# 08usb.net
KiCad netlist of a schematic drawn in Altium Designer
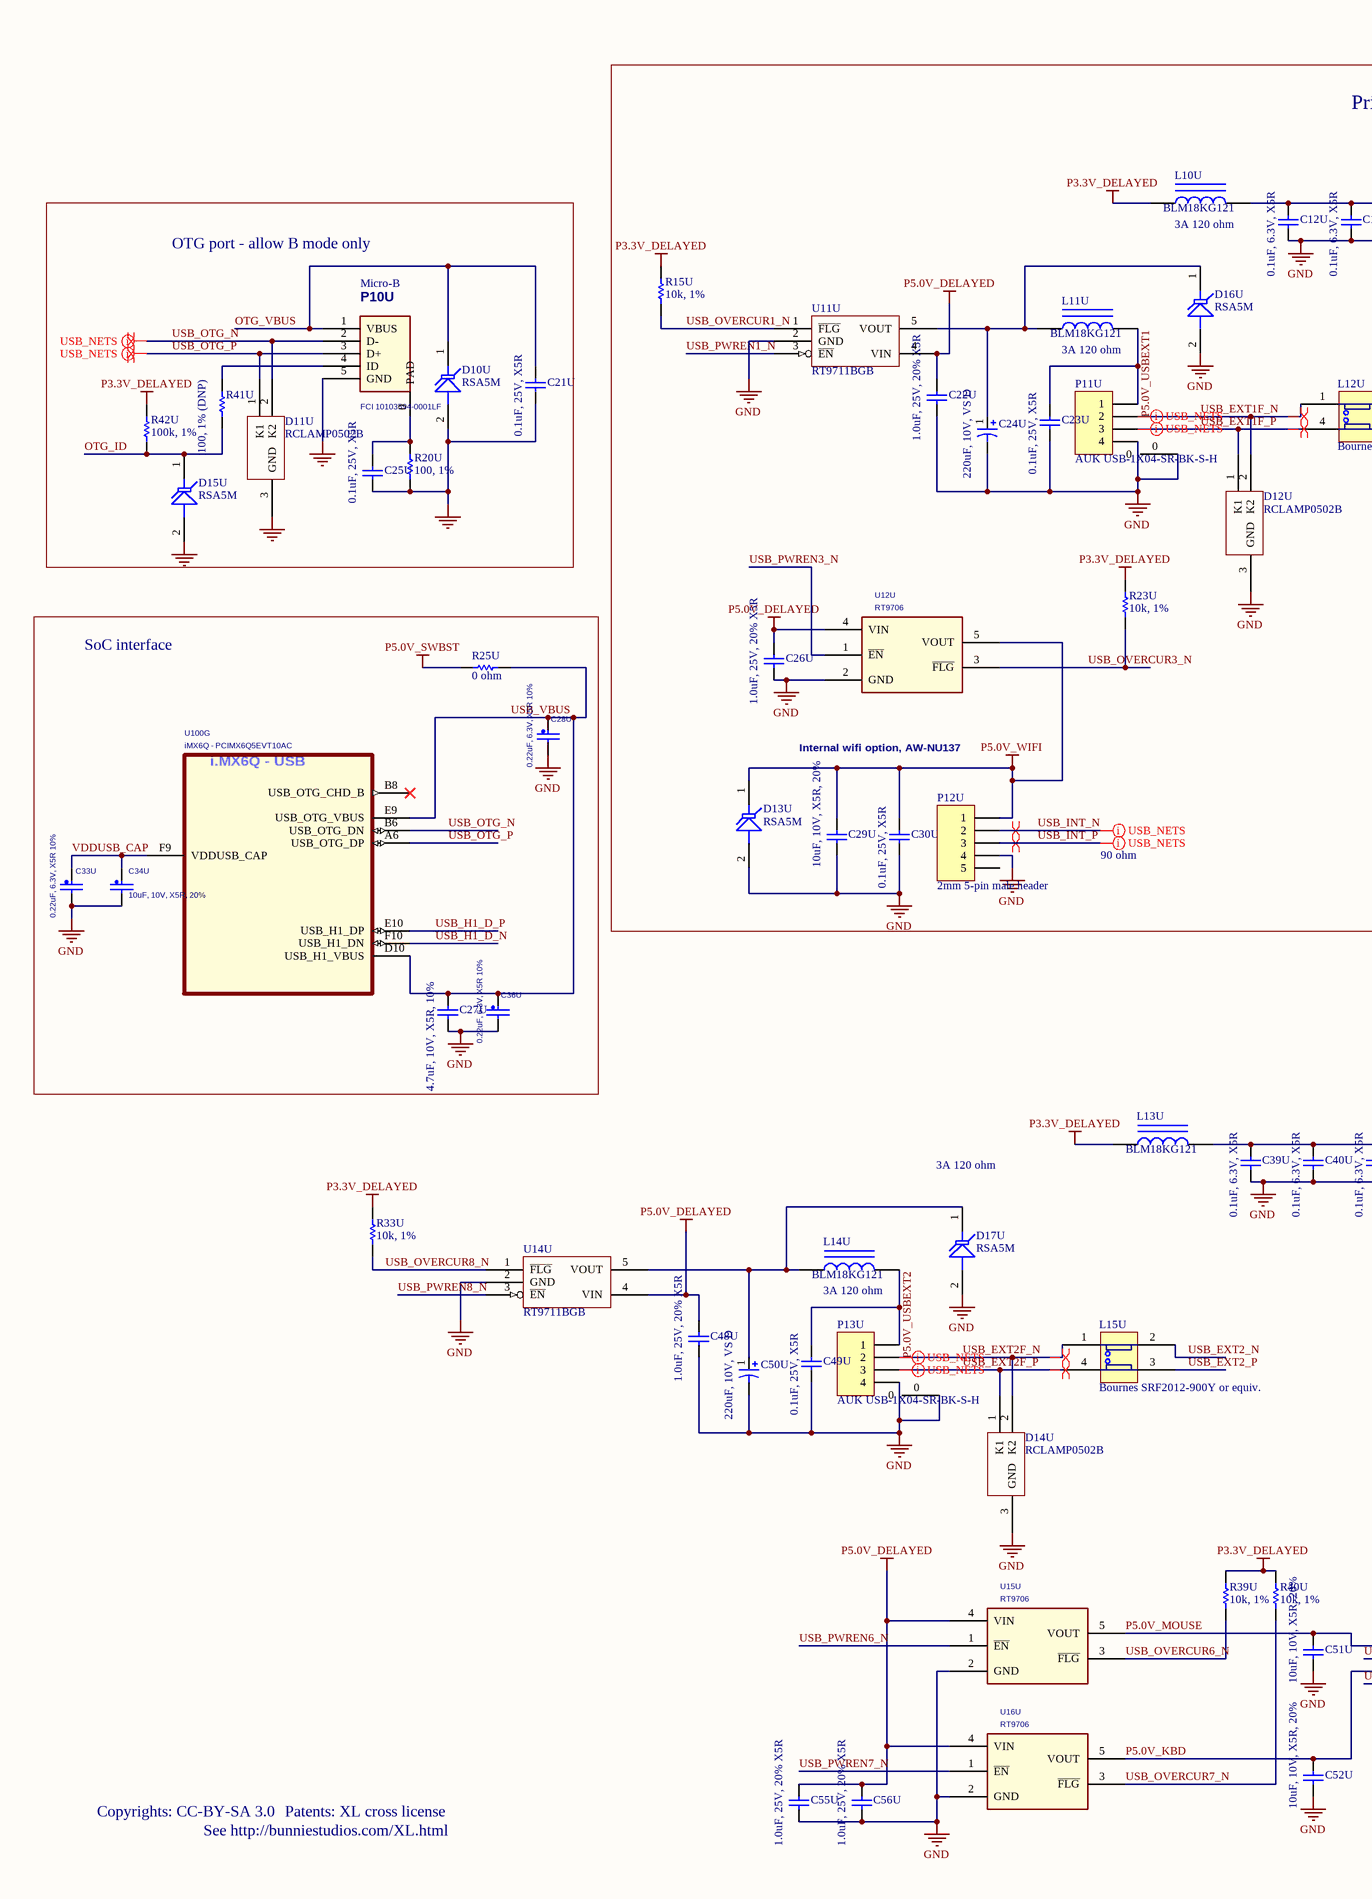
[diagram p0: 08usb.SchDoc, left]
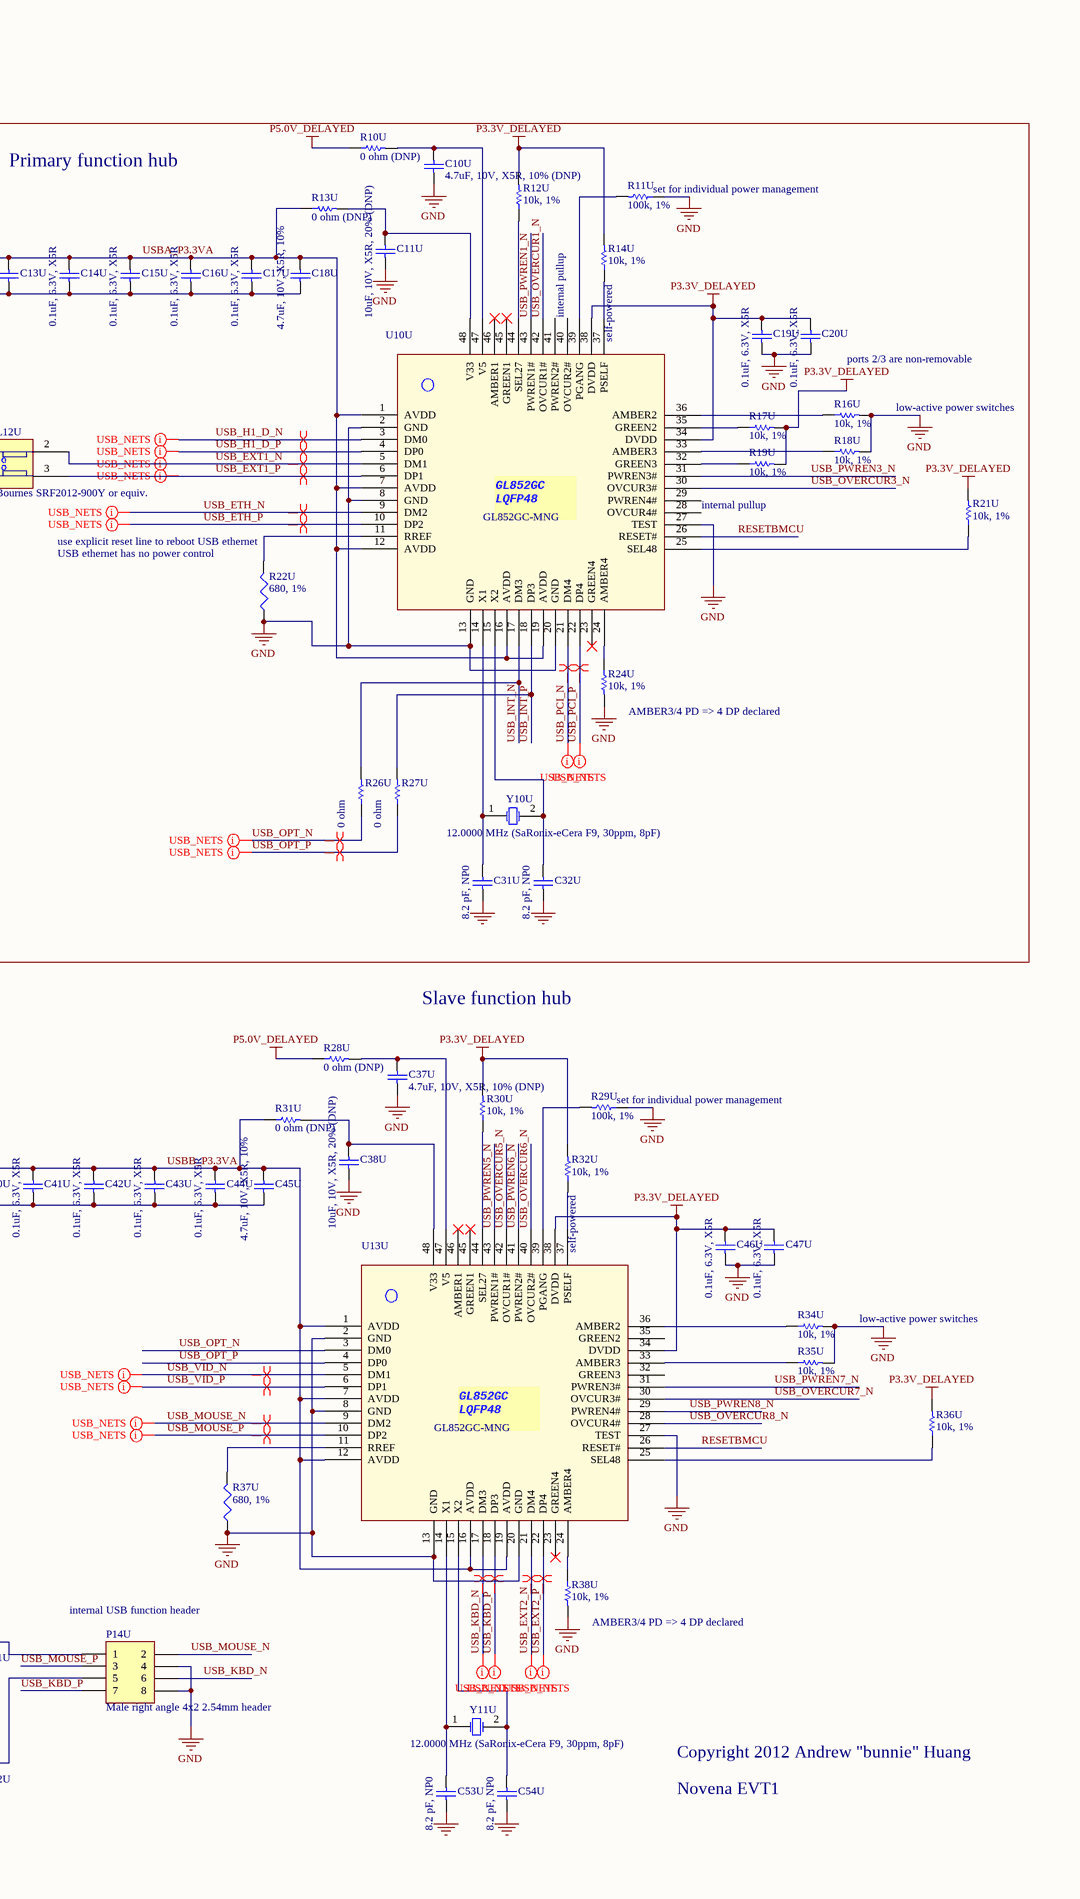
[diagram p1: 08usb.SchDoc, right]

(export (version "E")
  (design (tool "Eeschema 10.0.6"))
  (components
    (comp (ref "C10U")
      (value "4.7uF, 10V, X5R, 10% (DNP)")
      (footprint "CAPC1608N")
      (description "Capacitor (Semiconductor SIM Model)")
      (fields (field (name "PUBLISHER") "Altium Limited"))
      (libsource (lib "Miscellaneous Devices") (part "Cap Semi"))
    )
    (comp (ref "C11U")
      (value "10uF, 10V, X5R, 20% (DNP)")
      (footprint "CAPC1608N")
      (description "Capacitor (Semiconductor SIM Model)")
      (fields (field (name "PUBLISHER") "Altium Limited"))
      (libsource (lib "Miscellaneous Devices") (part "Cap Semi"))
    )
    (comp (ref "C12U")
      (value "0.1uF, 6.3V, X5R")
      (footprint "CAPC0603N_B")
      (description "Capacitor (Semiconductor SIM Model)")
      (fields (field (name "PUBLISHER") "Altium Limited"))
      (libsource (lib "Miscellaneous Devices") (part "Cap Semi"))
    )
    (comp (ref "C13U")
      (value "0.1uF, 6.3V, X5R")
      (footprint "CAPC0603N_B")
      (description "Capacitor (Semiconductor SIM Model)")
      (fields (field (name "PUBLISHER") "Altium Limited"))
      (libsource (lib "Miscellaneous Devices") (part "Cap Semi"))
    )
    (comp (ref "C14U")
      (value "0.1uF, 6.3V, X5R")
      (footprint "CAPC0603N_B")
      (description "Capacitor (Semiconductor SIM Model)")
      (fields (field (name "PUBLISHER") "Altium Limited"))
      (libsource (lib "Miscellaneous Devices") (part "Cap Semi"))
    )
    (comp (ref "C15U")
      (value "0.1uF, 6.3V, X5R")
      (footprint "CAPC0603N_B")
      (description "Capacitor (Semiconductor SIM Model)")
      (fields (field (name "PUBLISHER") "Altium Limited"))
      (libsource (lib "Miscellaneous Devices") (part "Cap Semi"))
    )
    (comp (ref "C16U")
      (value "0.1uF, 6.3V, X5R")
      (footprint "CAPC0603N_B")
      (description "Capacitor (Semiconductor SIM Model)")
      (fields (field (name "PUBLISHER") "Altium Limited"))
      (libsource (lib "Miscellaneous Devices") (part "Cap Semi"))
    )
    (comp (ref "C17U")
      (value "0.1uF, 6.3V, X5R")
      (footprint "CAPC0603N_B")
      (description "Capacitor (Semiconductor SIM Model)")
      (fields (field (name "PUBLISHER") "Altium Limited"))
      (libsource (lib "Miscellaneous Devices") (part "Cap Semi"))
    )
    (comp (ref "C18U")
      (value "4.7uF, 10V, X5R, 10%")
      (footprint "CAPC1608N")
      (description "Capacitor (Semiconductor SIM Model)")
      (fields (field (name "PUBLISHER") "Altium Limited"))
      (libsource (lib "Miscellaneous Devices") (part "Cap Semi"))
    )
    (comp (ref "C19U")
      (value "0.1uF, 6.3V, X5R")
      (footprint "CAPC0603N_B")
      (description "Capacitor (Semiconductor SIM Model)")
      (fields (field (name "PUBLISHER") "Altium Limited"))
      (libsource (lib "Miscellaneous Devices") (part "Cap Semi"))
    )
    (comp (ref "C20U")
      (value "0.1uF, 6.3V, X5R")
      (footprint "CAPC0603N_B")
      (description "Capacitor (Semiconductor SIM Model)")
      (fields (field (name "PUBLISHER") "Altium Limited"))
      (libsource (lib "Miscellaneous Devices") (part "Cap Semi"))
    )
    (comp (ref "C21U")
      (value "0.1uF, 25V, X5R")
      (footprint "CAPC1005N")
      (description "Capacitor (Semiconductor SIM Model)")
      (fields (field (name "PUBLISHER") "Altium Limited"))
      (libsource (lib "Miscellaneous Devices") (part "Cap Semi"))
    )
    (comp (ref "C22U")
      (value "1.0uF, 25V, 20% X5R")
      (footprint "CAPC1608N")
      (description "Capacitor (Semiconductor SIM Model)")
      (fields (field (name "PUBLISHER") "Altium Limited"))
      (libsource (lib "Miscellaneous Devices") (part "Cap Semi"))
    )
    (comp (ref "C23U")
      (value "0.1uF, 25V, X5R")
      (footprint "CAPC1005N")
      (description "Capacitor (Semiconductor SIM Model)")
      (fields (field (name "PUBLISHER") "Altium Limited"))
      (libsource (lib "Miscellaneous Devices") (part "Cap Semi"))
    )
    (comp (ref "C24U")
      (value "220uF, 10V, VS D")
      (footprint "6004pcb:ALCAP_D")
      (description "Polarized Capacitor (Surface Mount)")
      (fields (field (name "PUBLISHER") "Altium Limited"))
      (libsource (lib "Miscellaneous Devices") (part "Cap Pol3"))
    )
    (comp (ref "C25U")
      (value "0.1uF, 25V, X5R")
      (footprint "CAPC1005N")
      (description "Capacitor (Semiconductor SIM Model)")
      (fields (field (name "PUBLISHER") "Altium Limited"))
      (libsource (lib "Miscellaneous Devices") (part "Cap Semi"))
    )
    (comp (ref "C26U")
      (value "1.0uF, 25V, 20% X5R")
      (footprint "CAPC1608N")
      (description "Capacitor (Semiconductor SIM Model)")
      (fields (field (name "PUBLISHER") "Altium Limited"))
      (libsource (lib "Miscellaneous Devices") (part "Cap Semi"))
    )
    (comp (ref "C27U")
      (value "4.7uF, 10V, X5R, 10%")
      (footprint "CAPC1608N_HD")
      (description "Capacitor (Semiconductor SIM Model)")
      (fields (field (name "PUBLISHER") "Altium Limited"))
      (libsource (lib "Miscellaneous Devices") (part "Cap Semi"))
    )
    (comp (ref "C28U")
      (value "0.22uF, 6.3V, X5R 10%")
      (footprint "CAPC0603N_B")
      (description "CAP CER 0.01UF 6.3V 10% X7R 0201")
      (fields (field (name "TOLERANCE") "10%"))
      (libsource (lib "*") (part "CAP_NP_Dup1"))
    )
    (comp (ref "C29U")
      (value "10uF, 10V, X5R, 20%")
      (footprint "CAPC1608N")
      (description "Capacitor (Semiconductor SIM Model)")
      (fields (field (name "PUBLISHER") "Altium Limited"))
      (libsource (lib "Miscellaneous Devices") (part "Cap Semi"))
    )
    (comp (ref "C30U")
      (value "0.1uF, 25V, X5R")
      (footprint "CAPC1005N")
      (description "Capacitor (Semiconductor SIM Model)")
      (fields (field (name "PUBLISHER") "Altium Limited"))
      (libsource (lib "Miscellaneous Devices") (part "Cap Semi"))
    )
    (comp (ref "C31U")
      (value "8.2 pF, NP0")
      (footprint "CAPC1005N")
      (description "Capacitor (Semiconductor SIM Model)")
      (fields (field (name "PUBLISHER") "Altium Limited"))
      (libsource (lib "Miscellaneous Devices") (part "Cap Semi"))
    )
    (comp (ref "C32U")
      (value "8.2 pF, NP0")
      (footprint "CAPC1005N")
      (description "Capacitor (Semiconductor SIM Model)")
      (fields (field (name "PUBLISHER") "Altium Limited"))
      (libsource (lib "Miscellaneous Devices") (part "Cap Semi"))
    )
    (comp (ref "C33U")
      (value "0.22uF, 6.3V, X5R 10%")
      (footprint "CAPC0603N_B")
      (description "CAP CER 0.22UF 6.3V 20% X5R 0201")
      (fields (field (name "TOLERANCE") "20%"))
      (libsource (lib "*") (part "CAP_NP_Dup1"))
    )
    (comp (ref "C34U")
      (value "10uF, 10V, X5R, 20%")
      (footprint "CAPC1608N_HD")
      (description "CAP CER 10UF 6.3V 10% X5R 0603")
      (fields (field (name "TOLERANCE") "10%"))
      (libsource (lib "*") (part "CAP_NP_Dup1"))
    )
    (comp (ref "C36U")
      (value "0.22uF, 6.3V, X5R 10%")
      (footprint "CAPC0603N_B")
      (description "CAP CER 0.01UF 6.3V 10% X7R 0201")
      (fields (field (name "TOLERANCE") "10%"))
      (libsource (lib "*") (part "CAP_NP_Dup1"))
    )
    (comp (ref "C37U")
      (value "4.7uF, 10V, X5R, 10% (DNP)")
      (footprint "CAPC1608N")
      (description "Capacitor (Semiconductor SIM Model)")
      (fields (field (name "PUBLISHER") "Altium Limited"))
      (libsource (lib "Miscellaneous Devices") (part "Cap Semi"))
    )
    (comp (ref "C38U")
      (value "10uF, 10V, X5R, 20% (DNP)")
      (footprint "CAPC1608N")
      (description "Capacitor (Semiconductor SIM Model)")
      (fields (field (name "PUBLISHER") "Altium Limited"))
      (libsource (lib "Miscellaneous Devices") (part "Cap Semi"))
    )
    (comp (ref "C39U")
      (value "0.1uF, 6.3V, X5R")
      (footprint "CAPC0603N_B")
      (description "Capacitor (Semiconductor SIM Model)")
      (fields (field (name "PUBLISHER") "Altium Limited"))
      (libsource (lib "Miscellaneous Devices") (part "Cap Semi"))
    )
    (comp (ref "C40U")
      (value "0.1uF, 6.3V, X5R")
      (footprint "CAPC0603N_B")
      (description "Capacitor (Semiconductor SIM Model)")
      (fields (field (name "PUBLISHER") "Altium Limited"))
      (libsource (lib "Miscellaneous Devices") (part "Cap Semi"))
    )
    (comp (ref "C41U")
      (value "0.1uF, 6.3V, X5R")
      (footprint "CAPC0603N_B")
      (description "Capacitor (Semiconductor SIM Model)")
      (fields (field (name "PUBLISHER") "Altium Limited"))
      (libsource (lib "Miscellaneous Devices") (part "Cap Semi"))
    )
    (comp (ref "C42U")
      (value "0.1uF, 6.3V, X5R")
      (footprint "CAPC0603N_B")
      (description "Capacitor (Semiconductor SIM Model)")
      (fields (field (name "PUBLISHER") "Altium Limited"))
      (libsource (lib "Miscellaneous Devices") (part "Cap Semi"))
    )
    (comp (ref "C43U")
      (value "0.1uF, 6.3V, X5R")
      (footprint "CAPC0603N_B")
      (description "Capacitor (Semiconductor SIM Model)")
      (fields (field (name "PUBLISHER") "Altium Limited"))
      (libsource (lib "Miscellaneous Devices") (part "Cap Semi"))
    )
    (comp (ref "C44U")
      (value "0.1uF, 6.3V, X5R")
      (footprint "CAPC0603N_B")
      (description "Capacitor (Semiconductor SIM Model)")
      (fields (field (name "PUBLISHER") "Altium Limited"))
      (libsource (lib "Miscellaneous Devices") (part "Cap Semi"))
    )
    (comp (ref "C45U")
      (value "4.7uF, 10V, X5R, 10%")
      (footprint "CAPC1608N")
      (description "Capacitor (Semiconductor SIM Model)")
      (fields (field (name "PUBLISHER") "Altium Limited"))
      (libsource (lib "Miscellaneous Devices") (part "Cap Semi"))
    )
    (comp (ref "C46U")
      (value "0.1uF, 6.3V, X5R")
      (footprint "CAPC0603N_B")
      (description "Capacitor (Semiconductor SIM Model)")
      (fields (field (name "PUBLISHER") "Altium Limited"))
      (libsource (lib "Miscellaneous Devices") (part "Cap Semi"))
    )
    (comp (ref "C47U")
      (value "0.1uF, 6.3V, X5R")
      (footprint "CAPC0603N_B")
      (description "Capacitor (Semiconductor SIM Model)")
      (fields (field (name "PUBLISHER") "Altium Limited"))
      (libsource (lib "Miscellaneous Devices") (part "Cap Semi"))
    )
    (comp (ref "C48U")
      (value "1.0uF, 25V, 20% X5R")
      (footprint "CAPC1608N")
      (description "Capacitor (Semiconductor SIM Model)")
      (fields (field (name "PUBLISHER") "Altium Limited"))
      (libsource (lib "Miscellaneous Devices") (part "Cap Semi"))
    )
    (comp (ref "C49U")
      (value "0.1uF, 25V, X5R")
      (footprint "CAPC1005N")
      (description "Capacitor (Semiconductor SIM Model)")
      (fields (field (name "PUBLISHER") "Altium Limited"))
      (libsource (lib "Miscellaneous Devices") (part "Cap Semi"))
    )
    (comp (ref "C50U")
      (value "220uF, 10V, VS D")
      (footprint "6004pcb:ALCAP_D")
      (description "Polarized Capacitor (Surface Mount)")
      (fields (field (name "PUBLISHER") "Altium Limited"))
      (libsource (lib "Miscellaneous Devices") (part "Cap Pol3"))
    )
    (comp (ref "C51U")
      (value "10uF, 10V, X5R, 20%")
      (footprint "CAPC1608N")
      (description "Capacitor (Semiconductor SIM Model)")
      (fields (field (name "PUBLISHER") "Altium Limited"))
      (libsource (lib "Miscellaneous Devices") (part "Cap Semi"))
    )
    (comp (ref "C52U")
      (value "10uF, 10V, X5R, 20%")
      (footprint "CAPC1608N")
      (description "Capacitor (Semiconductor SIM Model)")
      (fields (field (name "PUBLISHER") "Altium Limited"))
      (libsource (lib "Miscellaneous Devices") (part "Cap Semi"))
    )
    (comp (ref "C53U")
      (value "8.2 pF, NP0")
      (footprint "CAPC1005N")
      (description "Capacitor (Semiconductor SIM Model)")
      (fields (field (name "PUBLISHER") "Altium Limited"))
      (libsource (lib "Miscellaneous Devices") (part "Cap Semi"))
    )
    (comp (ref "C54U")
      (value "8.2 pF, NP0")
      (footprint "CAPC1005N")
      (description "Capacitor (Semiconductor SIM Model)")
      (fields (field (name "PUBLISHER") "Altium Limited"))
      (libsource (lib "Miscellaneous Devices") (part "Cap Semi"))
    )
    (comp (ref "C55U")
      (value "1.0uF, 25V, 20% X5R")
      (footprint "CAPC1608N")
      (description "Capacitor (Semiconductor SIM Model)")
      (fields (field (name "PUBLISHER") "Altium Limited"))
      (libsource (lib "Miscellaneous Devices") (part "Cap Semi"))
    )
    (comp (ref "C56U")
      (value "1.0uF, 25V, 20% X5R")
      (footprint "CAPC1608N")
      (description "Capacitor (Semiconductor SIM Model)")
      (fields (field (name "PUBLISHER") "Altium Limited"))
      (libsource (lib "Miscellaneous Devices") (part "Cap Semi"))
    )
    (comp (ref "D10U")
      (value "RSA5M")
      (footprint "SOD123/X.85")
      (description "Tranzorb")
      (fields (field (name "PUBLISHER") "Altium Limited"))
      (libsource (lib "Miscellaneous Devices") (part "Tranzorb"))
    )
    (comp (ref "D11U")
      (value "RCLAMP0502B")
      (footprint "SOT-523")
      (description "2-channel ESD/CDE protection device for 5V devices")
      (libsource (lib "*") (part "RCLAMP0502B"))
    )
    (comp (ref "D12U")
      (value "RCLAMP0502B")
      (footprint "SOT-523")
      (description "2-channel ESD/CDE protection device for 5V devices")
      (libsource (lib "*") (part "RCLAMP0502B"))
    )
    (comp (ref "D13U")
      (value "RSA5M")
      (footprint "SOD123/X.85")
      (description "Tranzorb")
      (fields (field (name "PUBLISHER") "Altium Limited"))
      (libsource (lib "Miscellaneous Devices") (part "Tranzorb"))
    )
    (comp (ref "D14U")
      (value "RCLAMP0502B")
      (footprint "SOT-523")
      (description "2-channel ESD/CDE protection device for 5V devices")
      (libsource (lib "*") (part "RCLAMP0502B"))
    )
    (comp (ref "D15U")
      (value "RSA5M")
      (footprint "SOD123/X.85")
      (description "Tranzorb")
      (fields (field (name "PUBLISHER") "Altium Limited"))
      (libsource (lib "Miscellaneous Devices") (part "Tranzorb"))
    )
    (comp (ref "D16U")
      (value "RSA5M")
      (footprint "SOD123/X.85")
      (description "Tranzorb")
      (fields (field (name "PUBLISHER") "Altium Limited"))
      (libsource (lib "Miscellaneous Devices") (part "Tranzorb"))
    )
    (comp (ref "D17U")
      (value "RSA5M")
      (footprint "SOD123/X.85")
      (description "Tranzorb")
      (fields (field (name "PUBLISHER") "Altium Limited"))
      (libsource (lib "Miscellaneous Devices") (part "Tranzorb"))
    )
    (comp (ref "L10U")
      (value "BLM18KG121")
      (footprint "INDC1608AN")
      (description "Magnetic-Core Inductor")
      (fields (field (name "ALTIUM_VALUE") "3A 120 ohm") (field (name "PUBLISHER") "Altium Limited"))
      (libsource (lib "Miscellaneous Devices") (part "Inductor Iron"))
    )
    (comp (ref "L11U")
      (value "BLM18KG121")
      (footprint "INDC1608AN")
      (description "Magnetic-Core Inductor")
      (fields (field (name "ALTIUM_VALUE") "3A 120 ohm") (field (name "PUBLISHER") "Altium Limited"))
      (libsource (lib "Miscellaneous Devices") (part "Inductor Iron"))
    )
    (comp (ref "L12U")
      (value "Bournes SRF2012-900Y or equiv.")
      (footprint "USB_CM_CHOKE_0805")
      (description "USB common mode EMI choke (90 ohms)")
      (libsource (lib "commonsch") (part "USB_EMI_CHOKE"))
    )
    (comp (ref "L13U")
      (value "BLM18KG121")
      (footprint "INDC1608AN")
      (description "Magnetic-Core Inductor")
      (fields (field (name "ALTIUM_VALUE") "3A 120 ohm") (field (name "PUBLISHER") "Altium Limited"))
      (libsource (lib "Miscellaneous Devices") (part "Inductor Iron"))
    )
    (comp (ref "L14U")
      (value "BLM18KG121")
      (footprint "INDC1608AN")
      (description "Magnetic-Core Inductor")
      (fields (field (name "ALTIUM_VALUE") "3A 120 ohm") (field (name "PUBLISHER") "Altium Limited"))
      (libsource (lib "Miscellaneous Devices") (part "Inductor Iron"))
    )
    (comp (ref "L15U")
      (value "Bournes SRF2012-900Y or equiv.")
      (footprint "USB_CM_CHOKE_0805")
      (description "USB common mode EMI choke (90 ohms)")
      (libsource (lib "commonsch") (part "USB_EMI_CHOKE"))
    )
    (comp (ref "P10U")
      (value "FCI 10103594-0001LF")
      (footprint "USB_MICRO_B_SMT")
      (description "Micro USB B type connector, i.e. FCI 10103594")
      (libsource (lib "*") (part "USB_MINI-AB_1"))
    )
    (comp (ref "P11U")
      (value "AUK USB-1X04-SR-BK-S-H")
      (footprint "USB_TYPEA_TH_SINGLE")
      (description "Header, 4-Pin")
      (fields (field (name "PUBLISHER") "Altium Limited"))
      (libsource (lib "Miscellaneous Connectors") (part "Header 4"))
    )
    (comp (ref "P12U")
      (value "2mm 5-pin male header")
      (footprint "AW_NU137")
      (description "Two items: wifi card plus 5-pin, 2mm pitch male pin header, 3.5 to 4mm tall pins")
      (fields (field (name "PUBLISHER") "Altium Limited"))
      (libsource (lib "Miscellaneous Connectors") (part "Header 5"))
    )
    (comp (ref "P13U")
      (value "AUK USB-1X04-SR-BK-S-H")
      (footprint "USB_TYPEA_TH_SINGLE")
      (description "Header, 4-Pin")
      (fields (field (name "PUBLISHER") "Altium Limited"))
      (libsource (lib "Miscellaneous Connectors") (part "Header 4"))
    )
    (comp (ref "P14U")
      (value "Male right angle 4x2 2.54mm header")
      (footprint "HDR2X4H")
      (description "Header, 4-Pin, Dual row, Right Angle")
      (fields (field (name "PUBLISHER") "Altium Limited"))
      (libsource (lib "Miscellaneous Connectors") (part "Header 4X2H"))
    )
    (comp (ref "R10U")
      (value "0 ohm (DNP)")
      (footprint "RESC1005N")
      (description "Resistor")
      (fields (field (name "PUBLISHER") "Altium Limited"))
      (libsource (lib "Miscellaneous Devices") (part "Res1"))
    )
    (comp (ref "R11U")
      (value "100k, 1%")
      (footprint "RESC1005N")
      (description "Resistor")
      (fields (field (name "PUBLISHER") "Altium Limited"))
      (libsource (lib "Miscellaneous Devices") (part "Res1"))
    )
    (comp (ref "R12U")
      (value "10k, 1%")
      (footprint "RESC1005N")
      (description "Resistor")
      (fields (field (name "PUBLISHER") "Altium Limited"))
      (libsource (lib "Miscellaneous Devices") (part "Res1"))
    )
    (comp (ref "R13U")
      (value "0 ohm (DNP)")
      (footprint "RESC1005N")
      (description "Resistor")
      (fields (field (name "PUBLISHER") "Altium Limited"))
      (libsource (lib "Miscellaneous Devices") (part "Res1"))
    )
    (comp (ref "R14U")
      (value "10k, 1%")
      (footprint "RESC1005N")
      (description "Resistor")
      (fields (field (name "PUBLISHER") "Altium Limited"))
      (libsource (lib "Miscellaneous Devices") (part "Res1"))
    )
    (comp (ref "R15U")
      (value "10k, 1%")
      (footprint "RESC1005N")
      (description "Resistor")
      (fields (field (name "PUBLISHER") "Altium Limited"))
      (libsource (lib "Miscellaneous Devices") (part "Res1"))
    )
    (comp (ref "R16U")
      (value "10k, 1%")
      (footprint "RESC1005N")
      (description "Resistor")
      (fields (field (name "PUBLISHER") "Altium Limited"))
      (libsource (lib "Miscellaneous Devices") (part "Res1"))
    )
    (comp (ref "R17U")
      (value "10k, 1%")
      (footprint "RESC1005N")
      (description "Resistor")
      (fields (field (name "PUBLISHER") "Altium Limited"))
      (libsource (lib "Miscellaneous Devices") (part "Res1"))
    )
    (comp (ref "R18U")
      (value "10k, 1%")
      (footprint "RESC1005N")
      (description "Resistor")
      (fields (field (name "PUBLISHER") "Altium Limited"))
      (libsource (lib "Miscellaneous Devices") (part "Res1"))
    )
    (comp (ref "R19U")
      (value "10k, 1%")
      (footprint "RESC1005N")
      (description "Resistor")
      (fields (field (name "PUBLISHER") "Altium Limited"))
      (libsource (lib "Miscellaneous Devices") (part "Res1"))
    )
    (comp (ref "R20U")
      (value "100, 1%")
      (footprint "RESC1005N")
      (description "Resistor")
      (fields (field (name "PUBLISHER") "Altium Limited"))
      (libsource (lib "Miscellaneous Devices") (part "Res1"))
    )
    (comp (ref "R21U")
      (value "10k, 1%")
      (footprint "RESC1005N")
      (description "Resistor")
      (fields (field (name "PUBLISHER") "Altium Limited"))
      (libsource (lib "Miscellaneous Devices") (part "Res1"))
    )
    (comp (ref "R22U")
      (value "680, 1%")
      (footprint "RESC1005N")
      (description "Resistor")
      (fields (field (name "PUBLISHER") "Altium Limited"))
      (libsource (lib "Miscellaneous Devices") (part "Res3"))
    )
    (comp (ref "R23U")
      (value "10k, 1%")
      (footprint "RESC1005N")
      (description "Resistor")
      (fields (field (name "PUBLISHER") "Altium Limited"))
      (libsource (lib "Miscellaneous Devices") (part "Res1"))
    )
    (comp (ref "R24U")
      (value "10k, 1%")
      (footprint "RESC1005N")
      (description "Resistor")
      (fields (field (name "PUBLISHER") "Altium Limited"))
      (libsource (lib "Miscellaneous Devices") (part "Res1"))
    )
    (comp (ref "R25U")
      (value "0 ohm")
      (footprint "RESC1005N")
      (description "Resistor")
      (fields (field (name "PUBLISHER") "Altium Limited"))
      (libsource (lib "Miscellaneous Devices") (part "Res1"))
    )
    (comp (ref "R26U")
      (value "0 ohm")
      (footprint "RESC1005N")
      (description "Resistor")
      (fields (field (name "PUBLISHER") "Altium Limited"))
      (libsource (lib "Miscellaneous Devices") (part "Res1"))
    )
    (comp (ref "R27U")
      (value "0 ohm")
      (footprint "RESC1005N")
      (description "Resistor")
      (fields (field (name "PUBLISHER") "Altium Limited"))
      (libsource (lib "Miscellaneous Devices") (part "Res1"))
    )
    (comp (ref "R28U")
      (value "0 ohm (DNP)")
      (footprint "RESC1005N")
      (description "Resistor")
      (fields (field (name "PUBLISHER") "Altium Limited"))
      (libsource (lib "Miscellaneous Devices") (part "Res1"))
    )
    (comp (ref "R29U")
      (value "100k, 1%")
      (footprint "RESC1005N")
      (description "Resistor")
      (fields (field (name "PUBLISHER") "Altium Limited"))
      (libsource (lib "Miscellaneous Devices") (part "Res1"))
    )
    (comp (ref "R30U")
      (value "10k, 1%")
      (footprint "RESC1005N")
      (description "Resistor")
      (fields (field (name "PUBLISHER") "Altium Limited"))
      (libsource (lib "Miscellaneous Devices") (part "Res1"))
    )
    (comp (ref "R31U")
      (value "0 ohm (DNP)")
      (footprint "RESC1005N")
      (description "Resistor")
      (fields (field (name "PUBLISHER") "Altium Limited"))
      (libsource (lib "Miscellaneous Devices") (part "Res1"))
    )
    (comp (ref "R32U")
      (value "10k, 1%")
      (footprint "RESC1005N")
      (description "Resistor")
      (fields (field (name "PUBLISHER") "Altium Limited"))
      (libsource (lib "Miscellaneous Devices") (part "Res1"))
    )
    (comp (ref "R33U")
      (value "10k, 1%")
      (footprint "RESC1005N")
      (description "Resistor")
      (fields (field (name "PUBLISHER") "Altium Limited"))
      (libsource (lib "Miscellaneous Devices") (part "Res1"))
    )
    (comp (ref "R34U")
      (value "10k, 1%")
      (footprint "RESC1005N")
      (description "Resistor")
      (fields (field (name "PUBLISHER") "Altium Limited"))
      (libsource (lib "Miscellaneous Devices") (part "Res1"))
    )
    (comp (ref "R35U")
      (value "10k, 1%")
      (footprint "RESC1005N")
      (description "Resistor")
      (fields (field (name "PUBLISHER") "Altium Limited"))
      (libsource (lib "Miscellaneous Devices") (part "Res1"))
    )
    (comp (ref "R36U")
      (value "10k, 1%")
      (footprint "RESC1005N")
      (description "Resistor")
      (fields (field (name "PUBLISHER") "Altium Limited"))
      (libsource (lib "Miscellaneous Devices") (part "Res1"))
    )
    (comp (ref "R37U")
      (value "680, 1%")
      (footprint "RESC1005N")
      (description "Resistor")
      (fields (field (name "PUBLISHER") "Altium Limited"))
      (libsource (lib "Miscellaneous Devices") (part "Res3"))
    )
    (comp (ref "R38U")
      (value "10k, 1%")
      (footprint "RESC1005N")
      (description "Resistor")
      (fields (field (name "PUBLISHER") "Altium Limited"))
      (libsource (lib "Miscellaneous Devices") (part "Res1"))
    )
    (comp (ref "R39U")
      (value "10k, 1%")
      (footprint "RESC1005N")
      (description "Resistor")
      (fields (field (name "PUBLISHER") "Altium Limited"))
      (libsource (lib "Miscellaneous Devices") (part "Res1"))
    )
    (comp (ref "R40U")
      (value "10k, 1%")
      (footprint "RESC1005N")
      (description "Resistor")
      (fields (field (name "PUBLISHER") "Altium Limited"))
      (libsource (lib "Miscellaneous Devices") (part "Res1"))
    )
    (comp (ref "R41U")
      (value "100, 1% (DNP)")
      (footprint "RESC1005N")
      (description "Resistor")
      (fields (field (name "PUBLISHER") "Altium Limited"))
      (libsource (lib "Miscellaneous Devices") (part "Res1"))
    )
    (comp (ref "R42U")
      (value "100k, 1%")
      (footprint "RESC1005N")
      (description "Resistor")
      (fields (field (name "PUBLISHER") "Altium Limited"))
      (libsource (lib "Miscellaneous Devices") (part "Res1"))
    )
    (comp (ref "U10U")
      (value "GL852GC-MNG")
      (description "4-port multiple-TT hub with USB charging support")
      (libsource (lib "*") (part "GLI8024-48_4"))
    )
    (comp (ref "U11U")
      (value "RT9711BGB")
      (footprint "SOT23-5AN")
      (description "1.5A high-side power switch, active low enable")
      (libsource (lib "commonsch") (part "RT9711BGB"))
    )
    (comp (ref "U12U")
      (value "RT9706")
      (description "IC LIN SW W/FLAG 500MA 2.0-5.5V SOT23-5")
      (libsource (lib "*") (part "RT9706"))
    )
    (comp (ref "U13U")
      (value "GL852GC-MNG")
      (description "4-port multiple-TT hub with USB charging support")
      (libsource (lib "*") (part "GLI8024-48_4"))
    )
    (comp (ref "U14U")
      (value "RT9711BGB")
      (footprint "SOT23-5AN")
      (description "1.5A high-side power switch, active low enable")
      (libsource (lib "commonsch") (part "RT9711BGB"))
    )
    (comp (ref "U15U")
      (value "RT9706")
      (description "IC LIN SW W/FLAG 500MA 2.0-5.5V SOT23-5")
      (libsource (lib "*") (part "RT9706"))
    )
    (comp (ref "U16U")
      (value "RT9706")
      (description "IC LIN SW W/FLAG 500MA 2.0-5.5V SOT23-5")
      (libsource (lib "*") (part "RT9706"))
    )
    (comp (ref "U100")
      (value "iMX6Q - PCIMX6Q5EVT10AC")
      (description "PLACEHOLDER FOR FREESCALE PART NUMBER PMCIMX6Q6VV1A.")
      (libsource (lib "*") (part "PCIMX6Q6VV1A"))
    )
    (comp (ref "Y10U")
      (value "12.0000 MHz (SaRonix-eCera F9, 30ppm, 8pF)")
      (footprint "NDK_NX5032A")
      (description "Crystal Oscillator")
      (fields (field (name "PUBLISHER") "Altium Limited"))
      (libsource (lib "Miscellaneous Devices") (part "XTAL"))
    )
    (comp (ref "Y11U")
      (value "12.0000 MHz (SaRonix-eCera F9, 30ppm, 8pF)")
      (footprint "NDK_NX5032A")
      (description "Crystal Oscillator")
      (fields (field (name "PUBLISHER") "Altium Limited"))
      (libsource (lib "Miscellaneous Devices") (part "XTAL"))
    )
  )
  (nets
    (net (code "1") (name "/OTG_ID") (class "Default")
      (node (ref "D15U") (pin "1") (pinfunction "K_1") (pintype "passive"))
      (node (ref "R41U") (pin "1") (pinfunction "1_1") (pintype "passive"))
      (node (ref "R42U") (pin "1") (pinfunction "1_1") (pintype "passive"))
    )
    (net (code "2") (name "/OTG_VBUS") (class "Default")
      (node (ref "C21U") (pin "1") (pinfunction "1_1") (pintype "passive"))
      (node (ref "D10U") (pin "1") (pinfunction "K_1") (pintype "passive"))
      (node (ref "P10U") (pin "1") (pinfunction "VBUS_1") (pintype "passive"))
    )
    (net (code "3") (name "/P5.0V_KBD") (class "Default")
      (node (ref "C52U") (pin "1") (pinfunction "1_1") (pintype "passive"))
      (node (ref "P14U") (pin "5") (pinfunction "5_5") (pintype "passive"))
      (node (ref "U16U") (pin "5") (pinfunction "VOUT_5") (pintype "passive"))
    )
    (net (code "4") (name "/P5.0V_MOUSE") (class "Default")
      (node (ref "C51U") (pin "1") (pinfunction "1_1") (pintype "passive"))
      (node (ref "P14U") (pin "1") (pinfunction "1_1") (pintype "passive"))
      (node (ref "U15U") (pin "5") (pinfunction "VOUT_5") (pintype "passive"))
    )
    (net (code "5") (name "/P5.0V_USBEXT1") (class "Default")
      (node (ref "C23U") (pin "1") (pinfunction "1_1") (pintype "passive"))
      (node (ref "L11U") (pin "2") (pinfunction "2_2") (pintype "passive"))
      (node (ref "P11U") (pin "1") (pinfunction "1_1") (pintype "passive"))
    )
    (net (code "6") (name "/P5.0V_USBEXT2") (class "Default")
      (node (ref "C49U") (pin "1") (pinfunction "1_1") (pintype "passive"))
      (node (ref "L14U") (pin "2") (pinfunction "2_2") (pintype "passive"))
      (node (ref "P13U") (pin "1") (pinfunction "1_1") (pintype "passive"))
    )
    (net (code "7") (name "/RESETBMCU") (class "Default")
      (node (ref "U10U") (pin "26") (pinfunction "RESET#_26") (pintype "passive"))
      (node (ref "U13U") (pin "26") (pinfunction "RESET#_26") (pintype "passive"))
    )
    (net (code "8") (name "/USBA_P3.3VA") (class "Default")
      (node (ref "C12U") (pin "1") (pinfunction "1_1") (pintype "passive"))
      (node (ref "C13U") (pin "1") (pinfunction "1_1") (pintype "passive"))
      (node (ref "C14U") (pin "1") (pinfunction "1_1") (pintype "passive"))
      (node (ref "C15U") (pin "1") (pinfunction "1_1") (pintype "passive"))
      (node (ref "C16U") (pin "1") (pinfunction "1_1") (pintype "passive"))
      (node (ref "C17U") (pin "1") (pinfunction "1_1") (pintype "passive"))
      (node (ref "C18U") (pin "1") (pinfunction "1_1") (pintype "passive"))
      (node (ref "L10U") (pin "2") (pinfunction "2_2") (pintype "passive"))
      (node (ref "R13U") (pin "1") (pinfunction "1_1") (pintype "passive"))
      (node (ref "U10U") (pin "1") (pinfunction "AVDD_1") (pintype "passive"))
      (node (ref "U10U") (pin "12") (pinfunction "AVDD_12") (pintype "passive"))
      (node (ref "U10U") (pin "16") (pinfunction "AVDD_16") (pintype "passive"))
      (node (ref "U10U") (pin "19") (pinfunction "AVDD_19") (pintype "passive"))
      (node (ref "U10U") (pin "7") (pinfunction "AVDD_7") (pintype "passive"))
    )
    (net (code "9") (name "/USBB_P3.3VA") (class "Default")
      (node (ref "C39U") (pin "1") (pinfunction "1_1") (pintype "passive"))
      (node (ref "C40U") (pin "1") (pinfunction "1_1") (pintype "passive"))
      (node (ref "C41U") (pin "1") (pinfunction "1_1") (pintype "passive"))
      (node (ref "C42U") (pin "1") (pinfunction "1_1") (pintype "passive"))
      (node (ref "C43U") (pin "1") (pinfunction "1_1") (pintype "passive"))
      (node (ref "C44U") (pin "1") (pinfunction "1_1") (pintype "passive"))
      (node (ref "C45U") (pin "1") (pinfunction "1_1") (pintype "passive"))
      (node (ref "L13U") (pin "2") (pinfunction "2_2") (pintype "passive"))
      (node (ref "R31U") (pin "1") (pinfunction "1_1") (pintype "passive"))
      (node (ref "U13U") (pin "1") (pinfunction "AVDD_1") (pintype "passive"))
      (node (ref "U13U") (pin "12") (pinfunction "AVDD_12") (pintype "passive"))
      (node (ref "U13U") (pin "16") (pinfunction "AVDD_16") (pintype "passive"))
      (node (ref "U13U") (pin "19") (pinfunction "AVDD_19") (pintype "passive"))
      (node (ref "U13U") (pin "7") (pinfunction "AVDD_7") (pintype "passive"))
    )
    (net (code "10") (name "/USB_ETH_N") (class "Default")
      (node (ref "U10U") (pin "9") (pinfunction "DM2_9") (pintype "passive"))
    )
    (net (code "11") (name "/USB_ETH_P") (class "Default")
      (node (ref "U10U") (pin "10") (pinfunction "DP2_10") (pintype "passive"))
    )
    (net (code "12") (name "/USB_EXT1F_N") (class "Default")
      (node (ref "D12U") (pin "2") (pinfunction "K2_2") (pintype "passive"))
      (node (ref "L12U") (pin "1") (pinfunction "1_1") (pintype "passive"))
      (node (ref "P11U") (pin "2") (pinfunction "2_2") (pintype "passive"))
    )
    (net (code "13") (name "/USB_EXT1F_P") (class "Default")
      (node (ref "D12U") (pin "1") (pinfunction "K1_1") (pintype "passive"))
      (node (ref "L12U") (pin "4") (pinfunction "4_4") (pintype "passive"))
      (node (ref "P11U") (pin "3") (pinfunction "3_3") (pintype "passive"))
    )
    (net (code "14") (name "/USB_EXT1_N") (class "Default")
      (node (ref "L12U") (pin "2") (pinfunction "2_2") (pintype "passive"))
      (node (ref "U10U") (pin "5") (pinfunction "DM1_5") (pintype "passive"))
    )
    (net (code "15") (name "/USB_EXT1_P") (class "Default")
      (node (ref "L12U") (pin "3") (pinfunction "3_3") (pintype "passive"))
      (node (ref "U10U") (pin "6") (pinfunction "DP1_6") (pintype "passive"))
    )
    (net (code "16") (name "/USB_EXT2F_N") (class "Default")
      (node (ref "D14U") (pin "2") (pinfunction "K2_2") (pintype "passive"))
      (node (ref "L15U") (pin "1") (pinfunction "1_1") (pintype "passive"))
      (node (ref "P13U") (pin "2") (pinfunction "2_2") (pintype "passive"))
    )
    (net (code "17") (name "/USB_EXT2F_P") (class "Default")
      (node (ref "D14U") (pin "1") (pinfunction "K1_1") (pintype "passive"))
      (node (ref "L15U") (pin "4") (pinfunction "4_4") (pintype "passive"))
      (node (ref "P13U") (pin "3") (pinfunction "3_3") (pintype "passive"))
    )
    (net (code "18") (name "/USB_EXT2_N") (class "Default")
      (node (ref "L15U") (pin "2") (pinfunction "2_2") (pintype "passive"))
      (node (ref "U13U") (pin "21") (pinfunction "DM4_21") (pintype "passive"))
    )
    (net (code "19") (name "/USB_EXT2_P") (class "Default")
      (node (ref "L15U") (pin "3") (pinfunction "3_3") (pintype "passive"))
      (node (ref "U13U") (pin "22") (pinfunction "DP4_22") (pintype "passive"))
    )
    (net (code "20") (name "/USB_H1_D_N") (class "Default")
      (node (ref "U100") (pin "F10") (pinfunction "USB_H1_DN_F10") (pintype "bidirectional"))
      (node (ref "U10U") (pin "3") (pinfunction "DM0_3") (pintype "passive"))
    )
    (net (code "21") (name "/USB_H1_D_P") (class "Default")
      (node (ref "U100") (pin "E10") (pinfunction "USB_H1_DP_E10") (pintype "bidirectional"))
      (node (ref "U10U") (pin "4") (pinfunction "DP0_4") (pintype "passive"))
    )
    (net (code "22") (name "/USB_INT_N") (class "Default")
      (node (ref "P12U") (pin "2") (pinfunction "2_2") (pintype "passive"))
      (node (ref "R26U") (pin "2") (pinfunction "2_2") (pintype "passive"))
      (node (ref "U10U") (pin "17") (pinfunction "DM3_17") (pintype "passive"))
    )
    (net (code "23") (name "/USB_INT_P") (class "Default")
      (node (ref "P12U") (pin "3") (pinfunction "3_3") (pintype "passive"))
      (node (ref "R27U") (pin "2") (pinfunction "2_2") (pintype "passive"))
      (node (ref "U10U") (pin "18") (pinfunction "DP3_18") (pintype "passive"))
    )
    (net (code "24") (name "/USB_KBD_N") (class "Default")
      (node (ref "P14U") (pin "6") (pinfunction "6_6") (pintype "passive"))
      (node (ref "U13U") (pin "17") (pinfunction "DM3_17") (pintype "passive"))
    )
    (net (code "25") (name "/USB_KBD_P") (class "Default")
      (node (ref "P14U") (pin "7") (pinfunction "7_7") (pintype "passive"))
      (node (ref "U13U") (pin "18") (pinfunction "DP3_18") (pintype "passive"))
    )
    (net (code "26") (name "/USB_MOUSE_N") (class "Default")
      (node (ref "P14U") (pin "2") (pinfunction "2_2") (pintype "passive"))
      (node (ref "U13U") (pin "9") (pinfunction "DM2_9") (pintype "passive"))
    )
    (net (code "27") (name "/USB_MOUSE_P") (class "Default")
      (node (ref "P14U") (pin "3") (pinfunction "3_3") (pintype "passive"))
      (node (ref "U13U") (pin "10") (pinfunction "DP2_10") (pintype "passive"))
    )
    (net (code "28") (name "/USB_OPT_N") (class "Default")
      (node (ref "R26U") (pin "1") (pinfunction "1_1") (pintype "passive"))
      (node (ref "U13U") (pin "3") (pinfunction "DM0_3") (pintype "passive"))
    )
    (net (code "29") (name "/USB_OPT_P") (class "Default")
      (node (ref "R27U") (pin "1") (pinfunction "1_1") (pintype "passive"))
      (node (ref "U13U") (pin "4") (pinfunction "DP0_4") (pintype "passive"))
    )
    (net (code "30") (name "/USB_OTG_N") (class "Default")
      (node (ref "D11U") (pin "2") (pinfunction "K2_2") (pintype "passive"))
      (node (ref "P10U") (pin "2") (pinfunction "D-_2") (pintype "passive"))
      (node (ref "U100") (pin "B6") (pinfunction "USB_OTG_DN_B6") (pintype "bidirectional"))
    )
    (net (code "31") (name "/USB_OTG_P") (class "Default")
      (node (ref "D11U") (pin "1") (pinfunction "K1_1") (pintype "passive"))
      (node (ref "P10U") (pin "3") (pinfunction "D+_3") (pintype "passive"))
      (node (ref "U100") (pin "A6") (pinfunction "USB_OTG_DP_A6") (pintype "bidirectional"))
    )
    (net (code "32") (name "/USB_OVERCUR1_N") (class "Default")
      (node (ref "R15U") (pin "1") (pinfunction "1_1") (pintype "passive"))
      (node (ref "U10U") (pin "42") (pinfunction "OVCUR1#_42") (pintype "passive"))
      (node (ref "U11U") (pin "1") (pinfunction "~{FLG}_1") (pintype "open_collector"))
    )
    (net (code "33") (name "/USB_OVERCUR3_N") (class "Default")
      (node (ref "R23U") (pin "1") (pinfunction "1_1") (pintype "passive"))
      (node (ref "U10U") (pin "30") (pinfunction "OVCUR3#_30") (pintype "passive"))
      (node (ref "U12U") (pin "3") (pinfunction "~{FLG}_3") (pintype "passive"))
    )
    (net (code "34") (name "/USB_OVERCUR5_N") (class "Default")
      (node (ref "U13U") (pin "42") (pinfunction "OVCUR1#_42") (pintype "passive"))
    )
    (net (code "35") (name "/USB_OVERCUR6_N") (class "Default")
      (node (ref "R39U") (pin "2") (pinfunction "2_2") (pintype "passive"))
      (node (ref "U13U") (pin "40") (pinfunction "OVCUR2#_40") (pintype "passive"))
      (node (ref "U15U") (pin "3") (pinfunction "~{FLG}_3") (pintype "passive"))
    )
    (net (code "36") (name "/USB_OVERCUR7_N") (class "Default")
      (node (ref "R40U") (pin "2") (pinfunction "2_2") (pintype "passive"))
      (node (ref "U13U") (pin "30") (pinfunction "OVCUR3#_30") (pintype "passive"))
      (node (ref "U16U") (pin "3") (pinfunction "~{FLG}_3") (pintype "passive"))
    )
    (net (code "37") (name "/USB_OVERCUR8_N") (class "Default")
      (node (ref "R33U") (pin "1") (pinfunction "1_1") (pintype "passive"))
      (node (ref "U13U") (pin "28") (pinfunction "OVCUR4#_28") (pintype "passive"))
      (node (ref "U14U") (pin "1") (pinfunction "~{FLG}_1") (pintype "open_collector"))
    )
    (net (code "38") (name "/USB_PCI_N") (class "Default")
      (node (ref "U10U") (pin "21") (pinfunction "DM4_21") (pintype "passive"))
    )
    (net (code "39") (name "/USB_PCI_P") (class "Default")
      (node (ref "U10U") (pin "22") (pinfunction "DP4_22") (pintype "passive"))
    )
    (net (code "40") (name "/USB_PWREN1_N") (class "Default")
      (node (ref "U10U") (pin "43") (pinfunction "PWREN1#_43") (pintype "passive"))
      (node (ref "U11U") (pin "3") (pinfunction "~{EN}_3") (pintype "input"))
    )
    (net (code "41") (name "/USB_PWREN3_N") (class "Default")
      (node (ref "U10U") (pin "31") (pinfunction "PWREN3#_31") (pintype "passive"))
      (node (ref "U12U") (pin "1") (pinfunction "~{EN}_1") (pintype "passive"))
    )
    (net (code "42") (name "/USB_PWREN5_N") (class "Default")
      (node (ref "U13U") (pin "43") (pinfunction "PWREN1#_43") (pintype "passive"))
    )
    (net (code "43") (name "/USB_PWREN6_N") (class "Default")
      (node (ref "U13U") (pin "41") (pinfunction "PWREN2#_41") (pintype "passive"))
      (node (ref "U15U") (pin "1") (pinfunction "~{EN}_1") (pintype "passive"))
    )
    (net (code "44") (name "/USB_PWREN7_N") (class "Default")
      (node (ref "U13U") (pin "31") (pinfunction "PWREN3#_31") (pintype "passive"))
      (node (ref "U16U") (pin "1") (pinfunction "~{EN}_1") (pintype "passive"))
    )
    (net (code "45") (name "/USB_PWREN8_N") (class "Default")
      (node (ref "U13U") (pin "29") (pinfunction "PWREN4#_29") (pintype "passive"))
      (node (ref "U14U") (pin "3") (pinfunction "~{EN}_3") (pintype "input"))
    )
    (net (code "46") (name "/USB_VBUS") (class "Default")
      (node (ref "C27U") (pin "1") (pinfunction "1_1") (pintype "passive"))
      (node (ref "C28U") (pin "1") (pinfunction "1_1") (pintype "passive"))
      (node (ref "C36U") (pin "1") (pinfunction "1_1") (pintype "passive"))
      (node (ref "R25U") (pin "1") (pinfunction "1_1") (pintype "passive"))
      (node (ref "U100") (pin "D10") (pinfunction "USB_H1_VBUS_D10") (pintype "power_in"))
      (node (ref "U100") (pin "E9") (pinfunction "USB_OTG_VBUS_E9") (pintype "power_in"))
    )
    (net (code "47") (name "/USB_VID_N") (class "Default")
      (node (ref "U13U") (pin "5") (pinfunction "DM1_5") (pintype "passive"))
    )
    (net (code "48") (name "/USB_VID_P") (class "Default")
      (node (ref "U13U") (pin "6") (pinfunction "DP1_6") (pintype "passive"))
    )
    (net (code "49") (name "/VDDUSB_CAP") (class "Default")
      (node (ref "C33U") (pin "1") (pinfunction "1_1") (pintype "passive"))
      (node (ref "C34U") (pin "1") (pinfunction "1_1") (pintype "passive"))
      (node (ref "U100") (pin "F9") (pinfunction "VDDUSB_CAP_F9") (pintype "power_in"))
    )
    (net (code "50") (name "GND") (class "Default")
      (node (ref "C10U") (pin "2") (pinfunction "2_2") (pintype "passive"))
      (node (ref "C11U") (pin "2") (pinfunction "2_2") (pintype "passive"))
      (node (ref "C12U") (pin "2") (pinfunction "2_2") (pintype "passive"))
      (node (ref "C13U") (pin "2") (pinfunction "2_2") (pintype "passive"))
      (node (ref "C14U") (pin "2") (pinfunction "2_2") (pintype "passive"))
      (node (ref "C15U") (pin "2") (pinfunction "2_2") (pintype "passive"))
      (node (ref "C16U") (pin "2") (pinfunction "2_2") (pintype "passive"))
      (node (ref "C17U") (pin "2") (pinfunction "2_2") (pintype "passive"))
      (node (ref "C18U") (pin "2") (pinfunction "2_2") (pintype "passive"))
      (node (ref "C19U") (pin "2") (pinfunction "2_2") (pintype "passive"))
      (node (ref "C20U") (pin "2") (pinfunction "2_2") (pintype "passive"))
      (node (ref "C21U") (pin "2") (pinfunction "2_2") (pintype "passive"))
      (node (ref "C22U") (pin "2") (pinfunction "2_2") (pintype "passive"))
      (node (ref "C23U") (pin "2") (pinfunction "2_2") (pintype "passive"))
      (node (ref "C24U") (pin "2") (pinfunction "2_2") (pintype "passive"))
      (node (ref "C25U") (pin "2") (pinfunction "2_2") (pintype "passive"))
      (node (ref "C26U") (pin "2") (pinfunction "2_2") (pintype "passive"))
      (node (ref "C27U") (pin "2") (pinfunction "2_2") (pintype "passive"))
      (node (ref "C28U") (pin "2") (pinfunction "2_2") (pintype "passive"))
      (node (ref "C29U") (pin "2") (pinfunction "2_2") (pintype "passive"))
      (node (ref "C30U") (pin "2") (pinfunction "2_2") (pintype "passive"))
      (node (ref "C31U") (pin "2") (pinfunction "2_2") (pintype "passive"))
      (node (ref "C32U") (pin "2") (pinfunction "2_2") (pintype "passive"))
      (node (ref "C33U") (pin "2") (pinfunction "2_2") (pintype "passive"))
      (node (ref "C34U") (pin "2") (pinfunction "2_2") (pintype "passive"))
      (node (ref "C36U") (pin "2") (pinfunction "2_2") (pintype "passive"))
      (node (ref "C37U") (pin "2") (pinfunction "2_2") (pintype "passive"))
      (node (ref "C38U") (pin "2") (pinfunction "2_2") (pintype "passive"))
      (node (ref "C39U") (pin "2") (pinfunction "2_2") (pintype "passive"))
      (node (ref "C40U") (pin "2") (pinfunction "2_2") (pintype "passive"))
      (node (ref "C41U") (pin "2") (pinfunction "2_2") (pintype "passive"))
      (node (ref "C42U") (pin "2") (pinfunction "2_2") (pintype "passive"))
      (node (ref "C43U") (pin "2") (pinfunction "2_2") (pintype "passive"))
      (node (ref "C44U") (pin "2") (pinfunction "2_2") (pintype "passive"))
      (node (ref "C45U") (pin "2") (pinfunction "2_2") (pintype "passive"))
      (node (ref "C46U") (pin "2") (pinfunction "2_2") (pintype "passive"))
      (node (ref "C47U") (pin "2") (pinfunction "2_2") (pintype "passive"))
      (node (ref "C48U") (pin "2") (pinfunction "2_2") (pintype "passive"))
      (node (ref "C49U") (pin "2") (pinfunction "2_2") (pintype "passive"))
      (node (ref "C50U") (pin "2") (pinfunction "2_2") (pintype "passive"))
      (node (ref "C51U") (pin "2") (pinfunction "2_2") (pintype "passive"))
      (node (ref "C52U") (pin "2") (pinfunction "2_2") (pintype "passive"))
      (node (ref "C53U") (pin "2") (pinfunction "2_2") (pintype "passive"))
      (node (ref "C54U") (pin "2") (pinfunction "2_2") (pintype "passive"))
      (node (ref "C55U") (pin "2") (pinfunction "2_2") (pintype "passive"))
      (node (ref "C56U") (pin "2") (pinfunction "2_2") (pintype "passive"))
      (node (ref "D10U") (pin "2") (pinfunction "A_2") (pintype "passive"))
      (node (ref "D11U") (pin "3") (pinfunction "GND_3") (pintype "passive"))
      (node (ref "D12U") (pin "3") (pinfunction "GND_3") (pintype "passive"))
      (node (ref "D13U") (pin "2") (pinfunction "A_2") (pintype "passive"))
      (node (ref "D14U") (pin "3") (pinfunction "GND_3") (pintype "passive"))
      (node (ref "D15U") (pin "2") (pinfunction "A_2") (pintype "passive"))
      (node (ref "D16U") (pin "2") (pinfunction "A_2") (pintype "passive"))
      (node (ref "D17U") (pin "2") (pinfunction "A_2") (pintype "passive"))
      (node (ref "P10U") (pin "5") (pinfunction "GND_5") (pintype "passive"))
      (node (ref "P11U") (pin "0") (pinfunction "0_0") (pintype "passive"))
      (node (ref "P11U") (pin "4") (pinfunction "4_4") (pintype "passive"))
      (node (ref "P12U") (pin "4") (pinfunction "4_4") (pintype "passive"))
      (node (ref "P13U") (pin "0") (pinfunction "0_0") (pintype "passive"))
      (node (ref "P13U") (pin "4") (pinfunction "4_4") (pintype "passive"))
      (node (ref "P14U") (pin "4") (pinfunction "4_4") (pintype "passive"))
      (node (ref "P14U") (pin "8") (pinfunction "8_8") (pintype "passive"))
      (node (ref "R11U") (pin "1") (pinfunction "1_1") (pintype "passive"))
      (node (ref "R16U") (pin "2") (pinfunction "2_2") (pintype "passive"))
      (node (ref "R18U") (pin "2") (pinfunction "2_2") (pintype "passive"))
      (node (ref "R20U") (pin "2") (pinfunction "2_2") (pintype "passive"))
      (node (ref "R22U") (pin "1") (pinfunction "1_1") (pintype "passive"))
      (node (ref "R24U") (pin "2") (pinfunction "2_2") (pintype "passive"))
      (node (ref "R29U") (pin "1") (pinfunction "1_1") (pintype "passive"))
      (node (ref "R34U") (pin "2") (pinfunction "2_2") (pintype "passive"))
      (node (ref "R35U") (pin "2") (pinfunction "2_2") (pintype "passive"))
      (node (ref "R37U") (pin "1") (pinfunction "1_1") (pintype "passive"))
      (node (ref "R38U") (pin "2") (pinfunction "2_2") (pintype "passive"))
      (node (ref "U10U") (pin "13") (pinfunction "GND_13") (pintype "passive"))
      (node (ref "U10U") (pin "2") (pinfunction "GND_2") (pintype "passive"))
      (node (ref "U10U") (pin "20") (pinfunction "GND_20") (pintype "passive"))
      (node (ref "U10U") (pin "27") (pinfunction "TEST_27") (pintype "passive"))
      (node (ref "U10U") (pin "8") (pinfunction "GND_8") (pintype "passive"))
      (node (ref "U11U") (pin "2") (pinfunction "GND_2") (pintype "power_in"))
      (node (ref "U12U") (pin "2") (pinfunction "GND_2") (pintype "power_in"))
      (node (ref "U13U") (pin "13") (pinfunction "GND_13") (pintype "passive"))
      (node (ref "U13U") (pin "2") (pinfunction "GND_2") (pintype "passive"))
      (node (ref "U13U") (pin "20") (pinfunction "GND_20") (pintype "passive"))
      (node (ref "U13U") (pin "27") (pinfunction "TEST_27") (pintype "passive"))
      (node (ref "U13U") (pin "8") (pinfunction "GND_8") (pintype "passive"))
      (node (ref "U14U") (pin "2") (pinfunction "GND_2") (pintype "power_in"))
      (node (ref "U15U") (pin "2") (pinfunction "GND_2") (pintype "power_in"))
      (node (ref "U16U") (pin "2") (pinfunction "GND_2") (pintype "power_in"))
    )
    (net (code "51") (name "Net-(D16U-K)") (class "Default")
      (node (ref "C24U") (pin "1") (pinfunction "1_1") (pintype "passive"))
      (node (ref "D16U") (pin "1") (pinfunction "K_1") (pintype "passive"))
      (node (ref "L11U") (pin "1") (pinfunction "1_1") (pintype "passive"))
      (node (ref "U11U") (pin "5") (pinfunction "VOUT_5") (pintype "power_in"))
    )
    (net (code "52") (name "Net-(D17U-K)") (class "Default")
      (node (ref "C50U") (pin "1") (pinfunction "1_1") (pintype "passive"))
      (node (ref "D17U") (pin "1") (pinfunction "K_1") (pintype "passive"))
      (node (ref "L14U") (pin "1") (pinfunction "1_1") (pintype "passive"))
      (node (ref "U14U") (pin "5") (pinfunction "VOUT_5") (pintype "power_in"))
    )
    (net (code "53") (name "Net-(P10U-ID)") (class "Default")
      (node (ref "P10U") (pin "4") (pinfunction "ID_4") (pintype "passive"))
      (node (ref "R41U") (pin "2") (pinfunction "2_2") (pintype "passive"))
    )
    (net (code "54") (name "Net-(P10U-PAD)") (class "Default")
      (node (ref "C25U") (pin "1") (pinfunction "1_1") (pintype "passive"))
      (node (ref "P10U") (pin "0") (pinfunction "PAD_0") (pintype "passive"))
      (node (ref "R20U") (pin "1") (pinfunction "1_1") (pintype "passive"))
    )
    (net (code "55") (name "Net-(U10U-AMBER2)") (class "Default")
      (node (ref "R16U") (pin "1") (pinfunction "1_1") (pintype "passive"))
      (node (ref "U10U") (pin "36") (pinfunction "AMBER2_36") (pintype "passive"))
    )
    (net (code "56") (name "Net-(U10U-AMBER3)") (class "Default")
      (node (ref "R18U") (pin "1") (pinfunction "1_1") (pintype "passive"))
      (node (ref "U10U") (pin "33") (pinfunction "AMBER3_33") (pintype "passive"))
    )
    (net (code "57") (name "Net-(U10U-AMBER4)") (class "Default")
      (node (ref "R24U") (pin "1") (pinfunction "1_1") (pintype "passive"))
      (node (ref "U10U") (pin "24") (pinfunction "AMBER4_24") (pintype "passive"))
    )
    (net (code "58") (name "Net-(U10U-GREEN2)") (class "Default")
      (node (ref "R17U") (pin "1") (pinfunction "1_1") (pintype "passive"))
      (node (ref "U10U") (pin "35") (pinfunction "GREEN2_35") (pintype "passive"))
    )
    (net (code "59") (name "Net-(U10U-GREEN3)") (class "Default")
      (node (ref "R19U") (pin "1") (pinfunction "1_1") (pintype "passive"))
      (node (ref "U10U") (pin "32") (pinfunction "GREEN3_32") (pintype "passive"))
    )
    (net (code "60") (name "Net-(U10U-PGANG)") (class "Default")
      (node (ref "R11U") (pin "2") (pinfunction "2_2") (pintype "passive"))
      (node (ref "U10U") (pin "39") (pinfunction "PGANG_39") (pintype "passive"))
    )
    (net (code "61") (name "Net-(U10U-PSELF)") (class "Default")
      (node (ref "R14U") (pin "1") (pinfunction "1_1") (pintype "passive"))
      (node (ref "U10U") (pin "37") (pinfunction "PSELF_37") (pintype "passive"))
    )
    (net (code "62") (name "Net-(U10U-RREF)") (class "Default")
      (node (ref "R22U") (pin "2") (pinfunction "2_2") (pintype "passive"))
      (node (ref "U10U") (pin "11") (pinfunction "RREF_11") (pintype "passive"))
    )
    (net (code "63") (name "Net-(U10U-SEL27)") (class "Default")
      (node (ref "R12U") (pin "1") (pinfunction "1_1") (pintype "passive"))
      (node (ref "U10U") (pin "44") (pinfunction "SEL27_44") (pintype "passive"))
    )
    (net (code "64") (name "Net-(U10U-SEL48)") (class "Default")
      (node (ref "R21U") (pin "1") (pinfunction "1_1") (pintype "passive"))
      (node (ref "U10U") (pin "25") (pinfunction "SEL48_25") (pintype "passive"))
    )
    (net (code "65") (name "Net-(U10U-V5)") (class "Default")
      (node (ref "C10U") (pin "1") (pinfunction "1_1") (pintype "passive"))
      (node (ref "R10U") (pin "2") (pinfunction "2_2") (pintype "passive"))
      (node (ref "U10U") (pin "47") (pinfunction "V5_47") (pintype "passive"))
    )
    (net (code "66") (name "Net-(U10U-V33)") (class "Default")
      (node (ref "C11U") (pin "1") (pinfunction "1_1") (pintype "passive"))
      (node (ref "R13U") (pin "2") (pinfunction "2_2") (pintype "passive"))
      (node (ref "U10U") (pin "48") (pinfunction "V33_48") (pintype "passive"))
    )
    (net (code "67") (name "Net-(U10U-X1)") (class "Default")
      (node (ref "C31U") (pin "1") (pinfunction "1_1") (pintype "passive"))
      (node (ref "U10U") (pin "14") (pinfunction "X1_14") (pintype "passive"))
      (node (ref "Y10U") (pin "1") (pinfunction "OSC1_1") (pintype "passive"))
    )
    (net (code "68") (name "Net-(U10U-X2)") (class "Default")
      (node (ref "C32U") (pin "1") (pinfunction "1_1") (pintype "passive"))
      (node (ref "U10U") (pin "15") (pinfunction "X2_15") (pintype "passive"))
      (node (ref "Y10U") (pin "2") (pinfunction "OSC2_2") (pintype "passive"))
    )
    (net (code "69") (name "Net-(U13U-AMBER2)") (class "Default")
      (node (ref "R34U") (pin "1") (pinfunction "1_1") (pintype "passive"))
      (node (ref "U13U") (pin "36") (pinfunction "AMBER2_36") (pintype "passive"))
    )
    (net (code "70") (name "Net-(U13U-AMBER3)") (class "Default")
      (node (ref "R35U") (pin "1") (pinfunction "1_1") (pintype "passive"))
      (node (ref "U13U") (pin "33") (pinfunction "AMBER3_33") (pintype "passive"))
    )
    (net (code "71") (name "Net-(U13U-AMBER4)") (class "Default")
      (node (ref "R38U") (pin "1") (pinfunction "1_1") (pintype "passive"))
      (node (ref "U13U") (pin "24") (pinfunction "AMBER4_24") (pintype "passive"))
    )
    (net (code "72") (name "Net-(U13U-PGANG)") (class "Default")
      (node (ref "R29U") (pin "2") (pinfunction "2_2") (pintype "passive"))
      (node (ref "U13U") (pin "39") (pinfunction "PGANG_39") (pintype "passive"))
    )
    (net (code "73") (name "Net-(U13U-PSELF)") (class "Default")
      (node (ref "R32U") (pin "1") (pinfunction "1_1") (pintype "passive"))
      (node (ref "U13U") (pin "37") (pinfunction "PSELF_37") (pintype "passive"))
    )
    (net (code "74") (name "Net-(U13U-RREF)") (class "Default")
      (node (ref "R37U") (pin "2") (pinfunction "2_2") (pintype "passive"))
      (node (ref "U13U") (pin "11") (pinfunction "RREF_11") (pintype "passive"))
    )
    (net (code "75") (name "Net-(U13U-SEL27)") (class "Default")
      (node (ref "R30U") (pin "1") (pinfunction "1_1") (pintype "passive"))
      (node (ref "U13U") (pin "44") (pinfunction "SEL27_44") (pintype "passive"))
    )
    (net (code "76") (name "Net-(U13U-SEL48)") (class "Default")
      (node (ref "R36U") (pin "1") (pinfunction "1_1") (pintype "passive"))
      (node (ref "U13U") (pin "25") (pinfunction "SEL48_25") (pintype "passive"))
    )
    (net (code "77") (name "Net-(U13U-V5)") (class "Default")
      (node (ref "C37U") (pin "1") (pinfunction "1_1") (pintype "passive"))
      (node (ref "R28U") (pin "2") (pinfunction "2_2") (pintype "passive"))
      (node (ref "U13U") (pin "47") (pinfunction "V5_47") (pintype "passive"))
    )
    (net (code "78") (name "Net-(U13U-V33)") (class "Default")
      (node (ref "C38U") (pin "1") (pinfunction "1_1") (pintype "passive"))
      (node (ref "R31U") (pin "2") (pinfunction "2_2") (pintype "passive"))
      (node (ref "U13U") (pin "48") (pinfunction "V33_48") (pintype "passive"))
    )
    (net (code "79") (name "Net-(U13U-X1)") (class "Default")
      (node (ref "C53U") (pin "1") (pinfunction "1_1") (pintype "passive"))
      (node (ref "U13U") (pin "14") (pinfunction "X1_14") (pintype "passive"))
      (node (ref "Y11U") (pin "1") (pinfunction "OSC1_1") (pintype "passive"))
    )
    (net (code "80") (name "Net-(U13U-X2)") (class "Default")
      (node (ref "C54U") (pin "1") (pinfunction "1_1") (pintype "passive"))
      (node (ref "U13U") (pin "15") (pinfunction "X2_15") (pintype "passive"))
      (node (ref "Y11U") (pin "2") (pinfunction "OSC2_2") (pintype "passive"))
    )
    (net (code "81") (name "P3.3V_DELAYED") (class "Default")
      (node (ref "C19U") (pin "1") (pinfunction "1_1") (pintype "passive"))
      (node (ref "C20U") (pin "1") (pinfunction "1_1") (pintype "passive"))
      (node (ref "C46U") (pin "1") (pinfunction "1_1") (pintype "passive"))
      (node (ref "C47U") (pin "1") (pinfunction "1_1") (pintype "passive"))
      (node (ref "L10U") (pin "1") (pinfunction "1_1") (pintype "passive"))
      (node (ref "L13U") (pin "1") (pinfunction "1_1") (pintype "passive"))
      (node (ref "R12U") (pin "2") (pinfunction "2_2") (pintype "passive"))
      (node (ref "R14U") (pin "2") (pinfunction "2_2") (pintype "passive"))
      (node (ref "R15U") (pin "2") (pinfunction "2_2") (pintype "passive"))
      (node (ref "R17U") (pin "2") (pinfunction "2_2") (pintype "passive"))
      (node (ref "R19U") (pin "2") (pinfunction "2_2") (pintype "passive"))
      (node (ref "R21U") (pin "2") (pinfunction "2_2") (pintype "passive"))
      (node (ref "R23U") (pin "2") (pinfunction "2_2") (pintype "passive"))
      (node (ref "R30U") (pin "2") (pinfunction "2_2") (pintype "passive"))
      (node (ref "R32U") (pin "2") (pinfunction "2_2") (pintype "passive"))
      (node (ref "R33U") (pin "2") (pinfunction "2_2") (pintype "passive"))
      (node (ref "R36U") (pin "2") (pinfunction "2_2") (pintype "passive"))
      (node (ref "R39U") (pin "1") (pinfunction "1_1") (pintype "passive"))
      (node (ref "R40U") (pin "1") (pinfunction "1_1") (pintype "passive"))
      (node (ref "R42U") (pin "2") (pinfunction "2_2") (pintype "passive"))
      (node (ref "U10U") (pin "34") (pinfunction "DVDD_34") (pintype "passive"))
      (node (ref "U10U") (pin "38") (pinfunction "DVDD_38") (pintype "passive"))
      (node (ref "U13U") (pin "34") (pinfunction "DVDD_34") (pintype "passive"))
      (node (ref "U13U") (pin "38") (pinfunction "DVDD_38") (pintype "passive"))
    )
    (net (code "82") (name "P5.0V_DELAYED") (class "Default")
      (node (ref "C22U") (pin "1") (pinfunction "1_1") (pintype "passive"))
      (node (ref "C26U") (pin "1") (pinfunction "1_1") (pintype "passive"))
      (node (ref "C48U") (pin "1") (pinfunction "1_1") (pintype "passive"))
      (node (ref "C55U") (pin "1") (pinfunction "1_1") (pintype "passive"))
      (node (ref "C56U") (pin "1") (pinfunction "1_1") (pintype "passive"))
      (node (ref "R10U") (pin "1") (pinfunction "1_1") (pintype "passive"))
      (node (ref "R28U") (pin "1") (pinfunction "1_1") (pintype "passive"))
      (node (ref "U11U") (pin "4") (pinfunction "VIN_4") (pintype "power_in"))
      (node (ref "U12U") (pin "4") (pinfunction "VIN_4") (pintype "passive"))
      (node (ref "U14U") (pin "4") (pinfunction "VIN_4") (pintype "power_in"))
      (node (ref "U15U") (pin "4") (pinfunction "VIN_4") (pintype "passive"))
      (node (ref "U16U") (pin "4") (pinfunction "VIN_4") (pintype "passive"))
    )
    (net (code "83") (name "P5.0V_SWBST") (class "Default")
      (node (ref "R25U") (pin "2") (pinfunction "2_2") (pintype "passive"))
    )
    (net (code "84") (name "P5.0V_WIFI") (class "Default")
      (node (ref "C29U") (pin "1") (pinfunction "1_1") (pintype "passive"))
      (node (ref "C30U") (pin "1") (pinfunction "1_1") (pintype "passive"))
      (node (ref "D13U") (pin "1") (pinfunction "K_1") (pintype "passive"))
      (node (ref "P12U") (pin "1") (pinfunction "1_1") (pintype "passive"))
      (node (ref "U12U") (pin "5") (pinfunction "VOUT_5") (pintype "passive"))
    )
    (net (code "85") (name "unconnected-(P12U-Pad5)") (class "Default")
      (node (ref "P12U") (pin "5") (pinfunction "5_5") (pintype "passive"))
    )
    (net (code "86") (name "unconnected-(U10U-AMBER1-Pad46)") (class "Default")
      (node (ref "U10U") (pin "46") (pinfunction "AMBER1_46") (pintype "passive+no_connect"))
    )
    (net (code "87") (name "unconnected-(U10U-GREEN1-Pad45)") (class "Default")
      (node (ref "U10U") (pin "45") (pinfunction "GREEN1_45") (pintype "passive+no_connect"))
    )
    (net (code "88") (name "unconnected-(U10U-GREEN4-Pad23)") (class "Default")
      (node (ref "U10U") (pin "23") (pinfunction "GREEN4_23") (pintype "passive+no_connect"))
    )
    (net (code "89") (name "unconnected-(U10U-OVCUR2#-Pad40)") (class "Default")
      (node (ref "U10U") (pin "40") (pinfunction "OVCUR2#_40") (pintype "passive"))
    )
    (net (code "90") (name "unconnected-(U10U-OVCUR4#-Pad28)") (class "Default")
      (node (ref "U10U") (pin "28") (pinfunction "OVCUR4#_28") (pintype "passive"))
    )
    (net (code "91") (name "unconnected-(U10U-PWREN2#-Pad41)") (class "Default")
      (node (ref "U10U") (pin "41") (pinfunction "PWREN2#_41") (pintype "passive"))
    )
    (net (code "92") (name "unconnected-(U10U-PWREN4#-Pad29)") (class "Default")
      (node (ref "U10U") (pin "29") (pinfunction "PWREN4#_29") (pintype "passive"))
    )
    (net (code "93") (name "unconnected-(U13U-AMBER1-Pad46)") (class "Default")
      (node (ref "U13U") (pin "46") (pinfunction "AMBER1_46") (pintype "passive+no_connect"))
    )
    (net (code "94") (name "unconnected-(U13U-GREEN1-Pad45)") (class "Default")
      (node (ref "U13U") (pin "45") (pinfunction "GREEN1_45") (pintype "passive+no_connect"))
    )
    (net (code "95") (name "unconnected-(U13U-GREEN2-Pad35)") (class "Default")
      (node (ref "U13U") (pin "35") (pinfunction "GREEN2_35") (pintype "passive"))
    )
    (net (code "96") (name "unconnected-(U13U-GREEN3-Pad32)") (class "Default")
      (node (ref "U13U") (pin "32") (pinfunction "GREEN3_32") (pintype "passive"))
    )
    (net (code "97") (name "unconnected-(U13U-GREEN4-Pad23)") (class "Default")
      (node (ref "U13U") (pin "23") (pinfunction "GREEN4_23") (pintype "passive+no_connect"))
    )
    (net (code "98") (name "unconnected-(U100G-USB_OTG_CHD_B-PadB8)") (class "Default")
      (node (ref "U100") (pin "B8") (pinfunction "USB_OTG_CHD_B_B8") (pintype "output+no_connect"))
    )
  )
)
